# rpifan.net
KiCad netlist of a schematic drawn in EAGLE
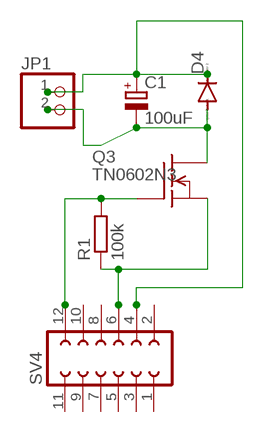
[diagram p0: schematic, sheet 1]

(export (version "E")
  (design (tool "Eeschema 10.0.6"))
  (components
    (comp (ref "C1")
      (value "100uF")
      (footprint "eagle-import:E2-5")
      (libsource (lib "eagle-import") (part "CPOL-EUE2-5"))
    )
    (comp (ref "D4")
      (value "DIODE-D-2.5")
      (footprint "eagle-import:D-2.5")
      (libsource (lib "eagle-import") (part "DIODE-D-2.5"))
    )
    (comp (ref "JP1")
      (value "PINHD-1X2")
      (footprint "eagle-import:1X02")
      (libsource (lib "eagle-import") (part "PINHD-1X2"))
    )
    (comp (ref "Q3")
      (value "TN0602N3")
      (footprint "eagle-import:TO-92")
      (libsource (lib "eagle-import") (part "TN0602N3"))
    )
    (comp (ref "R1")
      (value "100k")
      (footprint "eagle-import:0204_7")
      (libsource (lib "eagle-import") (part "R-EU_0204/7"))
    )
    (comp (ref "SV4")
      (value "FE06-2")
      (footprint "eagle-import:FE06-2")
      (libsource (lib "eagle-import") (part "FE06-2"))
    )
  )
  (nets
    (net (code "1") (name "Net-(C1-Pad+)") (class "Default")
      (node (ref "C1") (pin "+") (pinfunction "+_+") (pintype "passive"))
      (node (ref "D4") (pin "C") (pinfunction "C_C") (pintype "passive"))
      (node (ref "JP1") (pin "1") (pinfunction "1_1") (pintype "passive"))
      (node (ref "SV4") (pin "4") (pinfunction "4_4") (pintype "passive"))
    )
    (net (code "2") (name "Net-(Q3-D)") (class "Default")
      (node (ref "C1") (pin "-") (pinfunction "-_-") (pintype "passive"))
      (node (ref "D4") (pin "A") (pinfunction "A_A") (pintype "passive"))
      (node (ref "JP1") (pin "2") (pinfunction "2_2") (pintype "passive"))
      (node (ref "Q3") (pin "3") (pinfunction "D_3") (pintype "passive"))
    )
    (net (code "3") (name "Net-(Q3-G)") (class "Default")
      (node (ref "Q3") (pin "2") (pinfunction "G_2") (pintype "passive"))
      (node (ref "R1") (pin "2") (pinfunction "2_2") (pintype "passive"))
      (node (ref "SV4") (pin "12") (pinfunction "12_12") (pintype "passive"))
    )
    (net (code "4") (name "Net-(Q3-S)") (class "Default")
      (node (ref "Q3") (pin "1") (pinfunction "S_1") (pintype "passive"))
      (node (ref "R1") (pin "1") (pinfunction "1_1") (pintype "passive"))
      (node (ref "SV4") (pin "6") (pinfunction "6_6") (pintype "passive"))
    )
    (net (code "5") (name "unconnected-(SV4-Pad1)") (class "Default")
      (node (ref "SV4") (pin "1") (pinfunction "1_1") (pintype "passive"))
    )
    (net (code "6") (name "unconnected-(SV4-Pad2)") (class "Default")
      (node (ref "SV4") (pin "2") (pinfunction "2_2") (pintype "passive"))
    )
    (net (code "7") (name "unconnected-(SV4-Pad3)") (class "Default")
      (node (ref "SV4") (pin "3") (pinfunction "3_3") (pintype "passive"))
    )
    (net (code "8") (name "unconnected-(SV4-Pad5)") (class "Default")
      (node (ref "SV4") (pin "5") (pinfunction "5_5") (pintype "passive"))
    )
    (net (code "9") (name "unconnected-(SV4-Pad7)") (class "Default")
      (node (ref "SV4") (pin "7") (pinfunction "7_7") (pintype "passive"))
    )
    (net (code "10") (name "unconnected-(SV4-Pad8)") (class "Default")
      (node (ref "SV4") (pin "8") (pinfunction "8_8") (pintype "passive"))
    )
    (net (code "11") (name "unconnected-(SV4-Pad9)") (class "Default")
      (node (ref "SV4") (pin "9") (pinfunction "9_9") (pintype "passive"))
    )
    (net (code "12") (name "unconnected-(SV4-Pad10)") (class "Default")
      (node (ref "SV4") (pin "10") (pinfunction "10_10") (pintype "passive"))
    )
    (net (code "13") (name "unconnected-(SV4-Pad11)") (class "Default")
      (node (ref "SV4") (pin "11") (pinfunction "11_11") (pintype "passive"))
    )
  )
)
